# USBdimmer.net
KiCad netlist of a schematic drawn in EAGLE
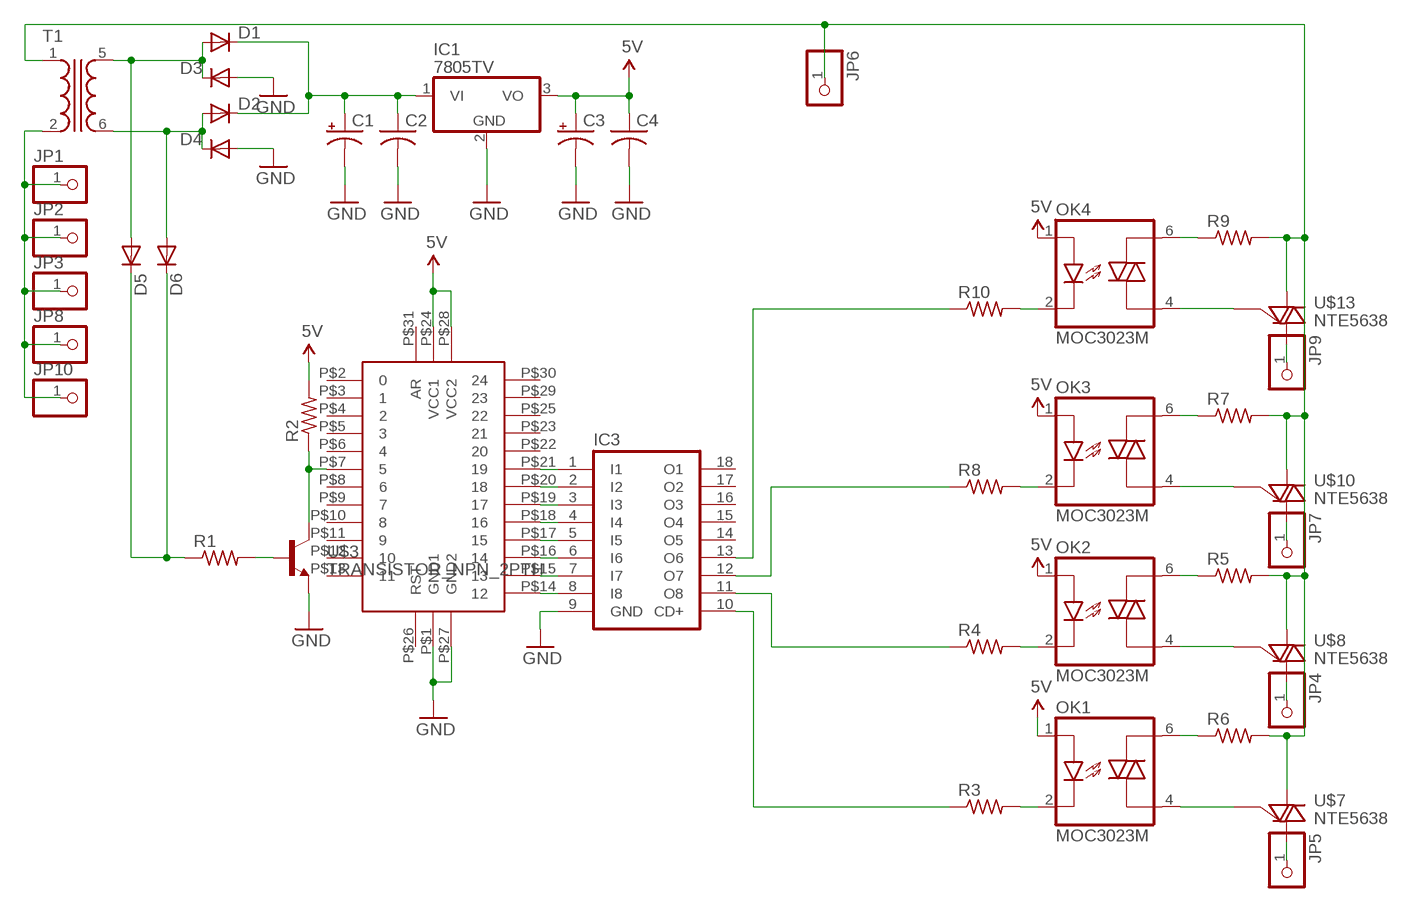
[diagram p0: schematic, sheet 1]

(export (version "E")
  (design (tool "Eeschema 10.0.6"))
  (components
    (comp (ref "C1")
      (value "CPOL-USE3.5-10")
      (footprint "eagle-import:E3,5-10")
      (libsource (lib "eagle-import") (part "CPOL-USE3.5-10"))
    )
    (comp (ref "C2")
      (value "C-US025-030X050")
      (footprint "eagle-import:C025-030X050")
      (libsource (lib "eagle-import") (part "C-US025-030X050"))
    )
    (comp (ref "C3")
      (value "CPOL-USE3.5-10")
      (footprint "eagle-import:E3,5-10")
      (libsource (lib "eagle-import") (part "CPOL-USE3.5-10"))
    )
    (comp (ref "C4")
      (value "C-US025-030X050")
      (footprint "eagle-import:C025-030X050")
      (libsource (lib "eagle-import") (part "C-US025-030X050"))
    )
    (comp (ref "D1")
      (value "DIODEPTH")
      (footprint "eagle-import:DIODE-1N4001")
      (libsource (lib "eagle-import") (part "DIODEPTH"))
    )
    (comp (ref "D2")
      (value "DIODEPTH")
      (footprint "eagle-import:DIODE-1N4001")
      (libsource (lib "eagle-import") (part "DIODEPTH"))
    )
    (comp (ref "D3")
      (value "DIODEPTH")
      (footprint "eagle-import:DIODE-1N4001")
      (libsource (lib "eagle-import") (part "DIODEPTH"))
    )
    (comp (ref "D4")
      (value "DIODEPTH")
      (footprint "eagle-import:DIODE-1N4001")
      (libsource (lib "eagle-import") (part "DIODEPTH"))
    )
    (comp (ref "D5")
      (value "DIODE1N4148")
      (footprint "eagle-import:DIODE-1N4148")
      (libsource (lib "eagle-import") (part "DIODE1N4148"))
    )
    (comp (ref "D6")
      (value "DIODE1N4148")
      (footprint "eagle-import:DIODE-1N4148")
      (libsource (lib "eagle-import") (part "DIODE1N4148"))
    )
    (comp (ref "IC1")
      (value "7805TV")
      (footprint "eagle-import:TO220V")
      (libsource (lib "eagle-import") (part "78TV05"))
    )
    (comp (ref "IC3")
      (value "ULN2803A")
      (footprint "eagle-import:DIL18")
      (libsource (lib "eagle-import") (part "ULN2803A"))
    )
    (comp (ref "JP1")
      (value "PINHD-1X1")
      (footprint "eagle-import:1X01")
      (libsource (lib "eagle-import") (part "PINHD-1X1"))
    )
    (comp (ref "JP2")
      (value "PINHD-1X1")
      (footprint "eagle-import:1X01")
      (libsource (lib "eagle-import") (part "PINHD-1X1"))
    )
    (comp (ref "JP3")
      (value "PINHD-1X1")
      (footprint "eagle-import:1X01")
      (libsource (lib "eagle-import") (part "PINHD-1X1"))
    )
    (comp (ref "JP4")
      (value "PINHD-1X1")
      (footprint "eagle-import:1X01")
      (libsource (lib "eagle-import") (part "PINHD-1X1"))
    )
    (comp (ref "JP5")
      (value "PINHD-1X1")
      (footprint "eagle-import:1X01")
      (libsource (lib "eagle-import") (part "PINHD-1X1"))
    )
    (comp (ref "JP6")
      (value "PINHD-1X1")
      (footprint "eagle-import:1X01")
      (libsource (lib "eagle-import") (part "PINHD-1X1"))
    )
    (comp (ref "JP7")
      (value "PINHD-1X1")
      (footprint "eagle-import:1X01")
      (libsource (lib "eagle-import") (part "PINHD-1X1"))
    )
    (comp (ref "JP8")
      (value "PINHD-1X1")
      (footprint "eagle-import:1X01")
      (libsource (lib "eagle-import") (part "PINHD-1X1"))
    )
    (comp (ref "JP9")
      (value "PINHD-1X1")
      (footprint "eagle-import:1X01")
      (libsource (lib "eagle-import") (part "PINHD-1X1"))
    )
    (comp (ref "JP10")
      (value "PINHD-1X1")
      (footprint "eagle-import:1X01")
      (libsource (lib "eagle-import") (part "PINHD-1X1"))
    )
    (comp (ref "OK1")
      (value "MOC3023M")
      (footprint "eagle-import:DIL06")
      (fields (field (name "MF") "FAIRCHILD SEMICONDUCTOR") (field (name "MPN") "MOC3023-M"))
      (libsource (lib "eagle-import") (part "MOC30M23"))
    )
    (comp (ref "OK2")
      (value "MOC3023M")
      (footprint "eagle-import:DIL06")
      (fields (field (name "MF") "FAIRCHILD SEMICONDUCTOR") (field (name "MPN") "MOC3023-M"))
      (libsource (lib "eagle-import") (part "MOC30M23"))
    )
    (comp (ref "OK3")
      (value "MOC3023M")
      (footprint "eagle-import:DIL06")
      (fields (field (name "MF") "FAIRCHILD SEMICONDUCTOR") (field (name "MPN") "MOC3023-M"))
      (libsource (lib "eagle-import") (part "MOC30M23"))
    )
    (comp (ref "OK4")
      (value "MOC3023M")
      (footprint "eagle-import:DIL06")
      (fields (field (name "MF") "FAIRCHILD SEMICONDUCTOR") (field (name "MPN") "MOC3023-M"))
      (libsource (lib "eagle-import") (part "MOC30M23"))
    )
    (comp (ref "R1")
      (value "FLIPFLOP-RES")
      (footprint "eagle-import:0805-THM")
      (libsource (lib "eagle-import") (part "FLIPFLOP-RES"))
    )
    (comp (ref "R2")
      (value "FLIPFLOP-RES")
      (footprint "eagle-import:0805-THM")
      (libsource (lib "eagle-import") (part "FLIPFLOP-RES"))
    )
    (comp (ref "R3")
      (value "FLIPFLOP-RES")
      (footprint "eagle-import:0805-THM")
      (libsource (lib "eagle-import") (part "FLIPFLOP-RES"))
    )
    (comp (ref "R4")
      (value "FLIPFLOP-RES")
      (footprint "eagle-import:0805-THM")
      (libsource (lib "eagle-import") (part "FLIPFLOP-RES"))
    )
    (comp (ref "R5")
      (value "FLIPFLOP-RES")
      (footprint "eagle-import:0805-THM")
      (libsource (lib "eagle-import") (part "FLIPFLOP-RES"))
    )
    (comp (ref "R6")
      (value "FLIPFLOP-RES")
      (footprint "eagle-import:0805-THM")
      (libsource (lib "eagle-import") (part "FLIPFLOP-RES"))
    )
    (comp (ref "R7")
      (value "FLIPFLOP-RES")
      (footprint "eagle-import:0805-THM")
      (libsource (lib "eagle-import") (part "FLIPFLOP-RES"))
    )
    (comp (ref "R8")
      (value "FLIPFLOP-RES")
      (footprint "eagle-import:0805-THM")
      (libsource (lib "eagle-import") (part "FLIPFLOP-RES"))
    )
    (comp (ref "R9")
      (value "FLIPFLOP-RES")
      (footprint "eagle-import:0805-THM")
      (libsource (lib "eagle-import") (part "FLIPFLOP-RES"))
    )
    (comp (ref "R10")
      (value "FLIPFLOP-RES")
      (footprint "eagle-import:0805-THM")
      (libsource (lib "eagle-import") (part "FLIPFLOP-RES"))
    )
    (comp (ref "T1")
      (value "XFORMER")
      (footprint "eagle-import:T70-E")
      (libsource (lib "eagle-import") (part "XFORMER"))
    )
    (comp (ref "U$1")
      (value "TEENSY2")
      (footprint "eagle-import:TEENSY2")
      (libsource (lib "eagle-import") (part "TEENSY2"))
    )
    (comp (ref "U$3")
      (value "TRANSISTOR_NPN_2PTH")
      (footprint "eagle-import:TO-92")
      (libsource (lib "eagle-import") (part "TRANSISTOR_NPN_2PTH"))
    )
    (comp (ref "U$7")
      (value "NTE5638")
      (footprint "eagle-import:TO220BV")
      (libsource (lib "eagle-import") (part "NTE5638"))
    )
    (comp (ref "U$8")
      (value "NTE5638")
      (footprint "eagle-import:TO220BV")
      (libsource (lib "eagle-import") (part "NTE5638"))
    )
    (comp (ref "U$10")
      (value "NTE5638")
      (footprint "eagle-import:TO220BV")
      (libsource (lib "eagle-import") (part "NTE5638"))
    )
    (comp (ref "U$13")
      (value "NTE5638")
      (footprint "eagle-import:TO220BV")
      (libsource (lib "eagle-import") (part "NTE5638"))
    )
  )
  (nets
    (net (code "1") (name "5V") (class "Default")
      (node (ref "C3") (pin "+") (pinfunction "+_+") (pintype "passive"))
      (node (ref "C4") (pin "1") (pinfunction "1_1") (pintype "passive"))
      (node (ref "IC1") (pin "3") (pinfunction "VO_3") (pintype "passive"))
      (node (ref "OK1") (pin "1") (pinfunction "A_1") (pintype "input"))
      (node (ref "OK2") (pin "1") (pinfunction "A_1") (pintype "input"))
      (node (ref "OK3") (pin "1") (pinfunction "A_1") (pintype "input"))
      (node (ref "OK4") (pin "1") (pinfunction "A_1") (pintype "input"))
      (node (ref "R2") (pin "2") (pinfunction "2_2") (pintype "passive"))
      (node (ref "U$1") (pin "P$24") (pinfunction "VCC1_P$24") (pintype "bidirectional"))
      (node (ref "U$1") (pin "P$28") (pinfunction "VCC2_P$28") (pintype "bidirectional"))
    )
    (net (code "2") (name "GND") (class "Default")
      (node (ref "C1") (pin "-") (pinfunction "-_-") (pintype "passive"))
      (node (ref "C2") (pin "2") (pinfunction "2_2") (pintype "passive"))
      (node (ref "C3") (pin "-") (pinfunction "-_-") (pintype "passive"))
      (node (ref "C4") (pin "2") (pinfunction "2_2") (pintype "passive"))
      (node (ref "D3") (pin "A") (pinfunction "A_A") (pintype "passive"))
      (node (ref "D4") (pin "A") (pinfunction "A_A") (pintype "passive"))
      (node (ref "IC1") (pin "2") (pinfunction "GND_2") (pintype "passive"))
      (node (ref "IC3") (pin "9") (pinfunction "GND_9") (pintype "power_in"))
      (node (ref "U$1") (pin "P$1") (pinfunction "GND1_P$1") (pintype "bidirectional"))
      (node (ref "U$1") (pin "P$27") (pinfunction "GND2_P$27") (pintype "bidirectional"))
      (node (ref "U$3") (pin "3") (pinfunction "E_3") (pintype "passive"))
    )
    (net (code "3") (name "Net-(D5-PadC)") (class "Default")
      (node (ref "D5") (pin "C") (pinfunction "C_C") (pintype "passive"))
      (node (ref "D6") (pin "C") (pinfunction "C_C") (pintype "passive"))
      (node (ref "R1") (pin "1") (pinfunction "1_1") (pintype "passive"))
    )
    (net (code "4") (name "Net-(IC1-VI)") (class "Default")
      (node (ref "C1") (pin "+") (pinfunction "+_+") (pintype "passive"))
      (node (ref "C2") (pin "1") (pinfunction "1_1") (pintype "passive"))
      (node (ref "D1") (pin "C") (pinfunction "C_C") (pintype "passive"))
      (node (ref "D2") (pin "C") (pinfunction "C_C") (pintype "passive"))
      (node (ref "IC1") (pin "1") (pinfunction "VI_1") (pintype "input"))
    )
    (net (code "5") (name "Net-(IC3-CD+)") (class "Default")
      (node (ref "IC3") (pin "10") (pinfunction "CD+_10") (pintype "passive"))
      (node (ref "R3") (pin "1") (pinfunction "1_1") (pintype "passive"))
    )
    (net (code "6") (name "Net-(IC3-I1)") (class "Default")
      (node (ref "IC3") (pin "1") (pinfunction "I1_1") (pintype "input"))
      (node (ref "U$1") (pin "P$21") (pinfunction "19_P$21") (pintype "bidirectional"))
    )
    (net (code "7") (name "Net-(IC3-I2)") (class "Default")
      (node (ref "IC3") (pin "2") (pinfunction "I2_2") (pintype "input"))
      (node (ref "U$1") (pin "P$20") (pinfunction "18_P$20") (pintype "bidirectional"))
    )
    (net (code "8") (name "Net-(IC3-I3)") (class "Default")
      (node (ref "IC3") (pin "3") (pinfunction "I3_3") (pintype "input"))
      (node (ref "U$1") (pin "P$19") (pinfunction "17_P$19") (pintype "bidirectional"))
    )
    (net (code "9") (name "Net-(IC3-I4)") (class "Default")
      (node (ref "IC3") (pin "4") (pinfunction "I4_4") (pintype "input"))
      (node (ref "U$1") (pin "P$18") (pinfunction "16_P$18") (pintype "bidirectional"))
    )
    (net (code "10") (name "Net-(IC3-I5)") (class "Default")
      (node (ref "IC3") (pin "5") (pinfunction "I5_5") (pintype "input"))
      (node (ref "U$1") (pin "P$17") (pinfunction "15_P$17") (pintype "bidirectional"))
    )
    (net (code "11") (name "Net-(IC3-I6)") (class "Default")
      (node (ref "IC3") (pin "6") (pinfunction "I6_6") (pintype "input"))
      (node (ref "U$1") (pin "P$16") (pinfunction "14_P$16") (pintype "bidirectional"))
    )
    (net (code "12") (name "Net-(IC3-I7)") (class "Default")
      (node (ref "IC3") (pin "7") (pinfunction "I7_7") (pintype "input"))
      (node (ref "U$1") (pin "P$15") (pinfunction "13_P$15") (pintype "bidirectional"))
    )
    (net (code "13") (name "Net-(IC3-I8)") (class "Default")
      (node (ref "IC3") (pin "8") (pinfunction "I8_8") (pintype "input"))
      (node (ref "U$1") (pin "P$14") (pinfunction "12_P$14") (pintype "bidirectional"))
    )
    (net (code "14") (name "Net-(IC3-O6)") (class "Default")
      (node (ref "IC3") (pin "13") (pinfunction "O6_13") (pintype "open_collector"))
      (node (ref "R10") (pin "1") (pinfunction "1_1") (pintype "passive"))
    )
    (net (code "15") (name "Net-(IC3-O7)") (class "Default")
      (node (ref "IC3") (pin "12") (pinfunction "O7_12") (pintype "open_collector"))
      (node (ref "R8") (pin "1") (pinfunction "1_1") (pintype "passive"))
    )
    (net (code "16") (name "Net-(IC3-O8)") (class "Default")
      (node (ref "IC3") (pin "11") (pinfunction "O8_11") (pintype "open_collector"))
      (node (ref "R4") (pin "1") (pinfunction "1_1") (pintype "passive"))
    )
    (net (code "17") (name "Net-(OK1-C)") (class "Default")
      (node (ref "OK1") (pin "2") (pinfunction "C_2") (pintype "input"))
      (node (ref "R3") (pin "2") (pinfunction "2_2") (pintype "passive"))
    )
    (net (code "18") (name "Net-(OK1-MT1)") (class "Default")
      (node (ref "OK1") (pin "6") (pinfunction "MT1_6") (pintype "output"))
      (node (ref "R6") (pin "1") (pinfunction "1_1") (pintype "passive"))
    )
    (net (code "19") (name "Net-(OK1-MT2)") (class "Default")
      (node (ref "OK1") (pin "4") (pinfunction "MT2_4") (pintype "output"))
      (node (ref "U$7") (pin "3") (pinfunction "G_3") (pintype "input"))
    )
    (net (code "20") (name "Net-(OK2-C)") (class "Default")
      (node (ref "OK2") (pin "2") (pinfunction "C_2") (pintype "input"))
      (node (ref "R4") (pin "2") (pinfunction "2_2") (pintype "passive"))
    )
    (net (code "21") (name "Net-(OK2-MT1)") (class "Default")
      (node (ref "OK2") (pin "6") (pinfunction "MT1_6") (pintype "output"))
      (node (ref "R5") (pin "1") (pinfunction "1_1") (pintype "passive"))
    )
    (net (code "22") (name "Net-(OK2-MT2)") (class "Default")
      (node (ref "OK2") (pin "4") (pinfunction "MT2_4") (pintype "output"))
      (node (ref "U$8") (pin "3") (pinfunction "G_3") (pintype "input"))
    )
    (net (code "23") (name "Net-(OK3-C)") (class "Default")
      (node (ref "OK3") (pin "2") (pinfunction "C_2") (pintype "input"))
      (node (ref "R8") (pin "2") (pinfunction "2_2") (pintype "passive"))
    )
    (net (code "24") (name "Net-(OK3-MT1)") (class "Default")
      (node (ref "OK3") (pin "6") (pinfunction "MT1_6") (pintype "output"))
      (node (ref "R7") (pin "1") (pinfunction "1_1") (pintype "passive"))
    )
    (net (code "25") (name "Net-(OK3-MT2)") (class "Default")
      (node (ref "OK3") (pin "4") (pinfunction "MT2_4") (pintype "output"))
      (node (ref "U$10") (pin "3") (pinfunction "G_3") (pintype "input"))
    )
    (net (code "26") (name "Net-(OK4-C)") (class "Default")
      (node (ref "OK4") (pin "2") (pinfunction "C_2") (pintype "input"))
      (node (ref "R10") (pin "2") (pinfunction "2_2") (pintype "passive"))
    )
    (net (code "27") (name "Net-(OK4-MT1)") (class "Default")
      (node (ref "OK4") (pin "6") (pinfunction "MT1_6") (pintype "output"))
      (node (ref "R9") (pin "1") (pinfunction "1_1") (pintype "passive"))
    )
    (net (code "28") (name "Net-(OK4-MT2)") (class "Default")
      (node (ref "OK4") (pin "4") (pinfunction "MT2_4") (pintype "output"))
      (node (ref "U$13") (pin "3") (pinfunction "G_3") (pintype "input"))
    )
    (net (code "29") (name "Net-(T1A-P1)") (class "Default")
      (node (ref "JP6") (pin "1") (pinfunction "1_1") (pintype "passive"))
      (node (ref "R5") (pin "2") (pinfunction "2_2") (pintype "passive"))
      (node (ref "R6") (pin "2") (pinfunction "2_2") (pintype "passive"))
      (node (ref "R7") (pin "2") (pinfunction "2_2") (pintype "passive"))
      (node (ref "R9") (pin "2") (pinfunction "2_2") (pintype "passive"))
      (node (ref "T1") (pin "1") (pinfunction "P1_1") (pintype "passive"))
      (node (ref "U$10") (pin "1") (pinfunction "MT1_1") (pintype "output"))
      (node (ref "U$13") (pin "1") (pinfunction "MT1_1") (pintype "output"))
      (node (ref "U$7") (pin "1") (pinfunction "MT1_1") (pintype "output"))
      (node (ref "U$8") (pin "1") (pinfunction "MT1_1") (pintype "output"))
    )
    (net (code "30") (name "Net-(T1A-P2)") (class "Default")
      (node (ref "JP1") (pin "1") (pinfunction "1_1") (pintype "passive"))
      (node (ref "JP10") (pin "1") (pinfunction "1_1") (pintype "passive"))
      (node (ref "JP2") (pin "1") (pinfunction "1_1") (pintype "passive"))
      (node (ref "JP3") (pin "1") (pinfunction "1_1") (pintype "passive"))
      (node (ref "JP8") (pin "1") (pinfunction "1_1") (pintype "passive"))
      (node (ref "T1") (pin "2") (pinfunction "P2_2") (pintype "passive"))
    )
    (net (code "31") (name "Net-(T1A-S1)") (class "Default")
      (node (ref "D1") (pin "A") (pinfunction "A_A") (pintype "passive"))
      (node (ref "D3") (pin "C") (pinfunction "C_C") (pintype "passive"))
      (node (ref "D5") (pin "A") (pinfunction "A_A") (pintype "passive"))
      (node (ref "T1") (pin "5") (pinfunction "S1_5") (pintype "passive"))
    )
    (net (code "32") (name "Net-(T1A-S2)") (class "Default")
      (node (ref "D2") (pin "A") (pinfunction "A_A") (pintype "passive"))
      (node (ref "D4") (pin "C") (pinfunction "C_C") (pintype "passive"))
      (node (ref "D6") (pin "A") (pinfunction "A_A") (pintype "passive"))
      (node (ref "T1") (pin "6") (pinfunction "S2_6") (pintype "passive"))
    )
    (net (code "33") (name "Net-(U$1-5)") (class "Default")
      (node (ref "R2") (pin "1") (pinfunction "1_1") (pintype "passive"))
      (node (ref "U$1") (pin "P$7") (pinfunction "5_P$7") (pintype "bidirectional"))
      (node (ref "U$3") (pin "1") (pinfunction "C_1") (pintype "passive"))
    )
    (net (code "34") (name "Net-(U$3-B)") (class "Default")
      (node (ref "R1") (pin "2") (pinfunction "2_2") (pintype "passive"))
      (node (ref "U$3") (pin "2") (pinfunction "B_2") (pintype "passive"))
    )
    (net (code "35") (name "Net-(U$7-MT2)") (class "Default")
      (node (ref "JP5") (pin "1") (pinfunction "1_1") (pintype "passive"))
      (node (ref "U$7") (pin "2") (pinfunction "MT2_2") (pintype "output"))
    )
    (net (code "36") (name "Net-(U$8-MT2)") (class "Default")
      (node (ref "JP4") (pin "1") (pinfunction "1_1") (pintype "passive"))
      (node (ref "U$8") (pin "2") (pinfunction "MT2_2") (pintype "output"))
    )
    (net (code "37") (name "Net-(U$10-MT2)") (class "Default")
      (node (ref "JP7") (pin "1") (pinfunction "1_1") (pintype "passive"))
      (node (ref "U$10") (pin "2") (pinfunction "MT2_2") (pintype "output"))
    )
    (net (code "38") (name "Net-(U$13-MT2)") (class "Default")
      (node (ref "JP9") (pin "1") (pinfunction "1_1") (pintype "passive"))
      (node (ref "U$13") (pin "2") (pinfunction "MT2_2") (pintype "output"))
    )
    (net (code "39") (name "unconnected-(IC3-O1-Pad18)") (class "Default")
      (node (ref "IC3") (pin "18") (pinfunction "O1_18") (pintype "open_collector"))
    )
    (net (code "40") (name "unconnected-(IC3-O2-Pad17)") (class "Default")
      (node (ref "IC3") (pin "17") (pinfunction "O2_17") (pintype "open_collector"))
    )
    (net (code "41") (name "unconnected-(IC3-O3-Pad16)") (class "Default")
      (node (ref "IC3") (pin "16") (pinfunction "O3_16") (pintype "open_collector"))
    )
    (net (code "42") (name "unconnected-(IC3-O4-Pad15)") (class "Default")
      (node (ref "IC3") (pin "15") (pinfunction "O4_15") (pintype "open_collector"))
    )
    (net (code "43") (name "unconnected-(IC3-O5-Pad14)") (class "Default")
      (node (ref "IC3") (pin "14") (pinfunction "O5_14") (pintype "open_collector"))
    )
    (net (code "44") (name "unconnected-(U$1-0-PadP$2)") (class "Default")
      (node (ref "U$1") (pin "P$2") (pinfunction "0_P$2") (pintype "bidirectional"))
    )
    (net (code "45") (name "unconnected-(U$1-1-PadP$3)") (class "Default")
      (node (ref "U$1") (pin "P$3") (pinfunction "1_P$3") (pintype "bidirectional"))
    )
    (net (code "46") (name "unconnected-(U$1-2-PadP$4)") (class "Default")
      (node (ref "U$1") (pin "P$4") (pinfunction "2_P$4") (pintype "bidirectional"))
    )
    (net (code "47") (name "unconnected-(U$1-3-PadP$5)") (class "Default")
      (node (ref "U$1") (pin "P$5") (pinfunction "3_P$5") (pintype "bidirectional"))
    )
    (net (code "48") (name "unconnected-(U$1-4-PadP$6)") (class "Default")
      (node (ref "U$1") (pin "P$6") (pinfunction "4_P$6") (pintype "bidirectional"))
    )
    (net (code "49") (name "unconnected-(U$1-6-PadP$8)") (class "Default")
      (node (ref "U$1") (pin "P$8") (pinfunction "6_P$8") (pintype "bidirectional"))
    )
    (net (code "50") (name "unconnected-(U$1-7-PadP$9)") (class "Default")
      (node (ref "U$1") (pin "P$9") (pinfunction "7_P$9") (pintype "bidirectional"))
    )
    (net (code "51") (name "unconnected-(U$1-8-PadP$10)") (class "Default")
      (node (ref "U$1") (pin "P$10") (pinfunction "8_P$10") (pintype "bidirectional"))
    )
    (net (code "52") (name "unconnected-(U$1-9-PadP$11)") (class "Default")
      (node (ref "U$1") (pin "P$11") (pinfunction "9_P$11") (pintype "bidirectional"))
    )
    (net (code "53") (name "unconnected-(U$1-10-PadP$12)") (class "Default")
      (node (ref "U$1") (pin "P$12") (pinfunction "10_P$12") (pintype "bidirectional"))
    )
    (net (code "54") (name "unconnected-(U$1-11-PadP$13)") (class "Default")
      (node (ref "U$1") (pin "P$13") (pinfunction "11_P$13") (pintype "bidirectional"))
    )
    (net (code "55") (name "unconnected-(U$1-20-PadP$22)") (class "Default")
      (node (ref "U$1") (pin "P$22") (pinfunction "20_P$22") (pintype "bidirectional"))
    )
    (net (code "56") (name "unconnected-(U$1-21-PadP$23)") (class "Default")
      (node (ref "U$1") (pin "P$23") (pinfunction "21_P$23") (pintype "bidirectional"))
    )
    (net (code "57") (name "unconnected-(U$1-22-PadP$25)") (class "Default")
      (node (ref "U$1") (pin "P$25") (pinfunction "22_P$25") (pintype "bidirectional"))
    )
    (net (code "58") (name "unconnected-(U$1-23-PadP$29)") (class "Default")
      (node (ref "U$1") (pin "P$29") (pinfunction "23_P$29") (pintype "bidirectional"))
    )
    (net (code "59") (name "unconnected-(U$1-24-PadP$30)") (class "Default")
      (node (ref "U$1") (pin "P$30") (pinfunction "24_P$30") (pintype "bidirectional"))
    )
    (net (code "60") (name "unconnected-(U$1-AR-PadP$31)") (class "Default")
      (node (ref "U$1") (pin "P$31") (pinfunction "AR_P$31") (pintype "bidirectional"))
    )
    (net (code "61") (name "unconnected-(U$1-RST-PadP$26)") (class "Default")
      (node (ref "U$1") (pin "P$26") (pinfunction "RST_P$26") (pintype "bidirectional"))
    )
  )
)
